# USB-ESP32.net
KiCad netlist of a schematic drawn in Altium Designer
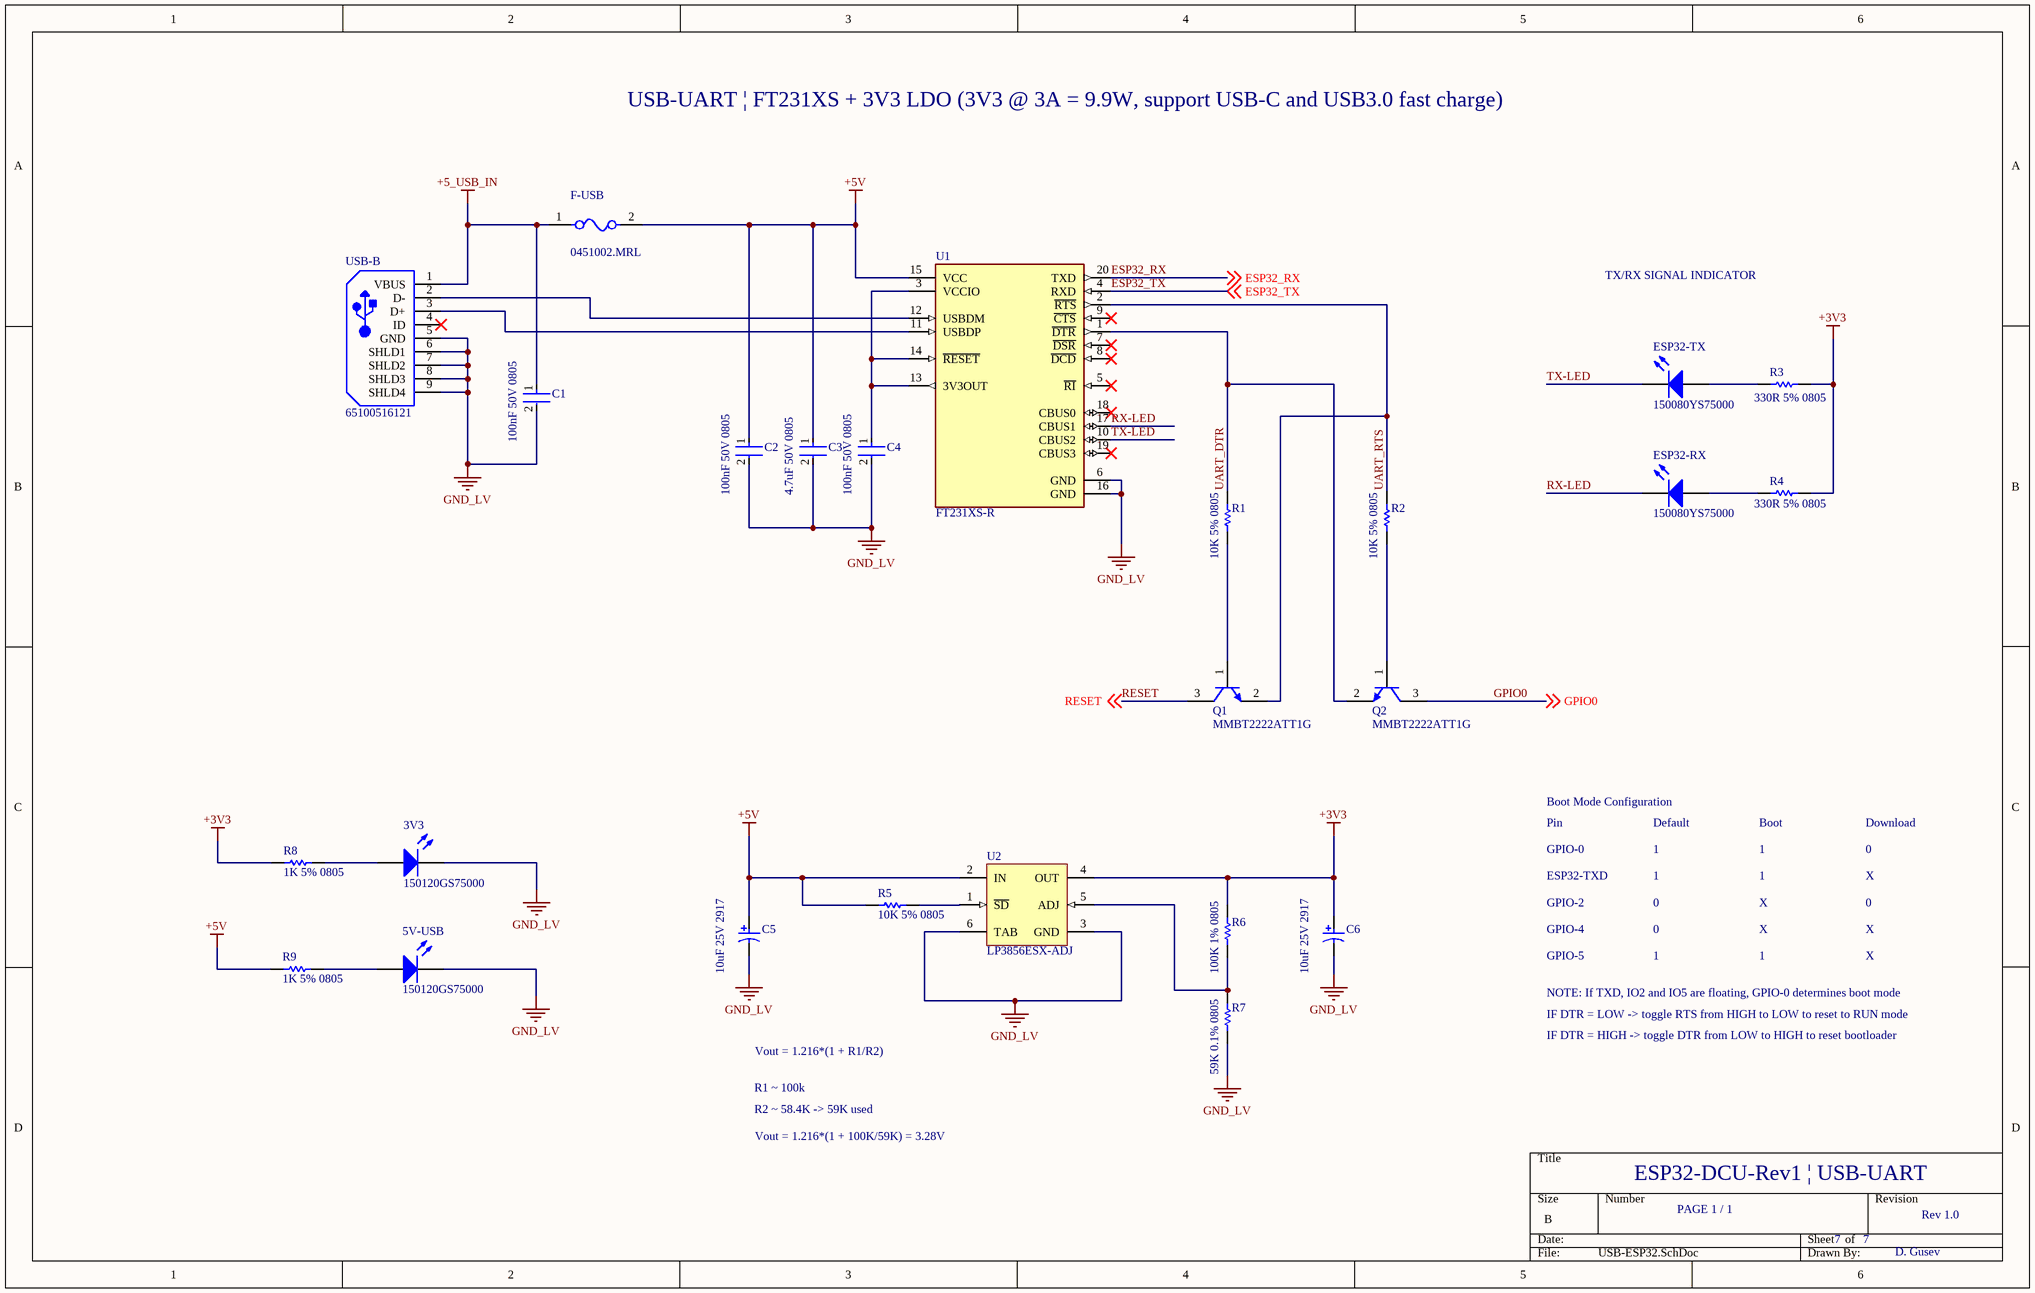
[diagram p0: USB-ESP32.SchDoc]

(export (version "E")
  (design (tool "Eeschema 10.0.6"))
  (components
    (comp (ref "3V3")
      (value "150120GS75000")
      (footprint "1206_A")
      (description "SMD mono-color Chip LED, WL-SMCW, Green")
      (fields (field (name "MANUFACTURER") "Wuerth Elektronik"))
      (libsource (lib "Altium Content Vault") (part "WE-LED_K1A2-2"))
    )
    (comp (ref "5V-USB")
      (value "150120GS75000")
      (footprint "1206_A")
      (description "SMD mono-color Chip LED, WL-SMCW, Green")
      (fields (field (name "MANUFACTURER") "Wuerth Elektronik"))
      (libsource (lib "Altium Content Vault") (part "WE-LED_K1A2-2"))
    )
    (comp (ref "C1")
      (value "100nF 50V 0805")
      (footprint "FP-C0805C-DN-MFG")
      (description "CAP CER 0.1UF 50V X7R 0805")
      (fields
        (field (name "MANUFACTURER PART NUMBER") "C0805C104K5RACTU")
        (field (name "MANUFACTURER") "KEMET")
      )
      (libsource (lib "Altium Content Vault") (part "b4654b650e69147ec39a6b967a45e02"))
    )
    (comp (ref "C2")
      (value "100nF 50V 0805")
      (footprint "FP-C0805C-DN-MFG")
      (description "CAP CER 0.1UF 50V X7R 0805")
      (fields
        (field (name "MANUFACTURER PART NUMBER") "C0805C104K5RACTU")
        (field (name "MANUFACTURER") "KEMET")
      )
      (libsource (lib "Altium Content Vault") (part "b4654b650e69147ec39a6b967a45e02"))
    )
    (comp (ref "C3")
      (value "4.7uF 50V 0805")
      (footprint "FP-C2012-125-MFG")
      (description "CAP CER 4.7UF 50V X5R 0805")
      (fields
        (field (name "TOLERANCE") "10%")
        (field (name "MANUFACTURER PART NUMBER") "C2012X5R1H475K125AB")
      )
      (libsource (lib "Altium Content Vault") (part "11868f565c42a9108669ba33697ecf6"))
    )
    (comp (ref "C4")
      (value "100nF 50V 0805")
      (footprint "FP-C0805C-DN-MFG")
      (description "CAP CER 0.1UF 50V X7R 0805")
      (fields
        (field (name "MANUFACTURER PART NUMBER") "C0805C104K5RACTU")
        (field (name "MANUFACTURER") "KEMET")
      )
      (libsource (lib "Altium Content Vault") (part "b4654b650e69147ec39a6b967a45e02"))
    )
    (comp (ref "C5")
      (value "10uF 25V 2917")
      (footprint "KEMT-T491-D_L")
      (description "Tantalum Capacitor, 10 uF, +/- 10%, 25 V, -55 to 125 degC, 2-Pin SMD, RoHS, Tape and Reel")
      (fields (field (name "MANUFACTURER") "Kemet") (field (name "VOLTAGE") "25VDC"))
      (libsource (lib "Altium Content Vault") (part "CAP-P-2"))
    )
    (comp (ref "C6")
      (value "10uF 25V 2917")
      (footprint "KEMT-T491-D_L")
      (description "Tantalum Capacitor, 10 uF, +/- 10%, 25 V, -55 to 125 degC, 2-Pin SMD, RoHS, Tape and Reel")
      (fields (field (name "MANUFACTURER") "Kemet") (field (name "VOLTAGE") "25VDC"))
      (libsource (lib "Altium Content Vault") (part "CAP-P-2"))
    )
    (comp (ref "ESP32-RX")
      (value "150080YS75000")
      (footprint "0805_A")
      (description "SMD mono-color Chip LED, WL-SMCW, Yellow")
      (fields (field (name "MANUFACTURER") "Wuerth Elektronik"))
      (libsource (lib "Altium Content Vault") (part "WE-LED_K1A2-2"))
    )
    (comp (ref "ESP32-TX")
      (value "150080YS75000")
      (footprint "0805_A")
      (description "SMD mono-color Chip LED, WL-SMCW, Yellow")
      (fields (field (name "MANUFACTURER") "Wuerth Elektronik"))
      (libsource (lib "Altium Content Vault") (part "WE-LED_K1A2-2"))
    )
    (comp (ref "F-USB")
      (value "0451002.MRL")
      (footprint "FP-0451-MFG")
      (description "FUSE BOARD MNT 2A 125VAC/VDC SMD")
      (fields
        (field (name "MANUFACTURER") "Littelfuse")
        (field (name "OCTOPART") "https://octopart.com/0451002.mrl-littelfuse-566376")
      )
      (libsource (lib "Altium Content Vault") (part "5bcf9b9f640e542cf0359d10258e979"))
    )
    (comp (ref "Q1")
      (value "MMBT2222ATT1G")
      (footprint "ONSC-SC-75-3-463-01_V")
      (description "General Purpose Transistor, NPN Silicon, 3-Pin SC-75, Pb-Free, Tape and Reel")
      (fields (field (name "MANUFACTURER") "On Semiconductor"))
      (libsource (lib "Altium Content Vault") (part "ONSC-NPN-B1E2C3-3"))
    )
    (comp (ref "Q2")
      (value "MMBT2222ATT1G")
      (footprint "ONSC-SC-75-3-463-01_V")
      (description "General Purpose Transistor, NPN Silicon, 3-Pin SC-75, Pb-Free, Tape and Reel")
      (fields (field (name "MANUFACTURER") "On Semiconductor"))
      (libsource (lib "Altium Content Vault") (part "ONSC-NPN-B1E2C3-3"))
    )
    (comp (ref "R1")
      (value "10K 5% 0805")
      (footprint "RESC2013X60X40ML20T25")
      (fields (field (name "PART NUMBER") "ERA6AEB123V") (field (name "MANUFACTURER") "Panasonic"))
      (libsource (lib "Altium Content Vault") (part "RES"))
    )
    (comp (ref "R2")
      (value "10K 5% 0805")
      (footprint "RESC2013X60X40ML20T25")
      (fields (field (name "PART NUMBER") "ERA6AEB123V") (field (name "MANUFACTURER") "Panasonic"))
      (libsource (lib "Altium Content Vault") (part "RES"))
    )
    (comp (ref "R3")
      (value "330R 5% 0805")
      (footprint "RESC2013X60X40ML20T25")
      (fields (field (name "PART NUMBER") "ERA6AEB123V") (field (name "MANUFACTURER") "Panasonic"))
      (libsource (lib "Altium Content Vault") (part "RES"))
    )
    (comp (ref "R4")
      (value "330R 5% 0805")
      (footprint "RESC2013X60X40ML20T25")
      (fields (field (name "PART NUMBER") "ERA6AEB123V") (field (name "MANUFACTURER") "Panasonic"))
      (libsource (lib "Altium Content Vault") (part "RES"))
    )
    (comp (ref "R5")
      (value "10K 5% 0805")
      (footprint "RESC2013X60X40ML20T25")
      (fields (field (name "PART NUMBER") "ERA6AEB123V") (field (name "MANUFACTURER") "Panasonic"))
      (libsource (lib "Altium Content Vault") (part "RES"))
    )
    (comp (ref "R6")
      (value "100K 1% 0805")
      (footprint "RESC2013X60X35ML10T20")
      (description "Chip Resistor, 100 KOhm, +/- 1%, 0.125 W, -55 to 155 degC, 0805 (2012 Metric), RoHS, Tape and Reel")
      (fields (field (name "MANUFACTURER") "Yageo") (field (name "TOLERANCE") "1%"))
      (libsource (lib "Altium Content Vault") (part "RES-2"))
    )
    (comp (ref "R7")
      (value "59K 0.1% 0805")
      (footprint "RESC2013X60X35NL10T20")
      (fields (field (name "PART NUMBER") "RC0805FR-0759KL") (field (name "MANUFACTURER") "Yageo"))
      (libsource (lib "Altium Content Vault") (part "RES"))
    )
    (comp (ref "R8")
      (value "1K 5% 0805")
      (footprint "RESC2013X60X40ML20T25")
      (fields (field (name "PART NUMBER") "ERA6AEB123V") (field (name "MANUFACTURER") "Panasonic"))
      (libsource (lib "Altium Content Vault") (part "RES"))
    )
    (comp (ref "R9")
      (value "1K 5% 0805")
      (footprint "RESC2013X60X40ML20T25")
      (fields (field (name "PART NUMBER") "ERA6AEB123V") (field (name "MANUFACTURER") "Panasonic"))
      (libsource (lib "Altium Content Vault") (part "RES"))
    )
    (comp (ref "U1")
      (value "FT231XS-R")
      (footprint "FP-SSOP-20-MFG")
      (description "IC USB SERIAL FULL UART 20SSOP")
      (libsource (lib "Altium Content Vault") (part "6ea930917329caabf1041b50a9b81b2"))
    )
    (comp (ref "U2")
      (value "LP3856ESX-ADJ")
      (footprint "TS5B_M")
      (description "3A Fast Ultra Low Dropout Linear Regulator, 5-pin TO-263")
      (fields (field (name "MANUFACTURER") "National Semiconductor"))
      (libsource (lib "Altium Content Vault") (part "PM-REG-LP3874ADJ-SIL6"))
    )
    (comp (ref "USB-B")
      (value "65100516121")
      (footprint "WE-65100516121_V")
      (description "MINI USB 2.0 SMT Type B 5 Contacts, 30 V, -40 to 105 degC, RoHS, Tape and Reel")
      (fields (field (name "MANUFACTURER") "Wuerth Elektronik"))
      (libsource (lib "Altium Content Vault") (part "USB-5-4SHLD"))
    )
  )
  (nets
    (net (code "1") (name "+3V3") (class "Default")
      (node (ref "C6") (pin "1") (pinfunction "1_1") (pintype "passive"))
      (node (ref "R3") (pin "1") (pinfunction "1_1") (pintype "passive"))
      (node (ref "R4") (pin "1") (pinfunction "1_1") (pintype "passive"))
      (node (ref "R6") (pin "2") (pinfunction "2_2") (pintype "passive"))
      (node (ref "R8") (pin "2") (pinfunction "2_2") (pintype "passive"))
      (node (ref "U2") (pin "4") (pinfunction "OUT_4") (pintype "power_in"))
    )
    (net (code "2") (name "+5V") (class "Default")
      (node (ref "C2") (pin "1") (pinfunction "1_1") (pintype "passive"))
      (node (ref "C3") (pin "1") (pinfunction "1_1") (pintype "passive"))
      (node (ref "C5") (pin "1") (pinfunction "1_1") (pintype "passive"))
      (node (ref "F-USB") (pin "2") (pinfunction "2_2") (pintype "passive"))
      (node (ref "R5") (pin "2") (pinfunction "2_2") (pintype "passive"))
      (node (ref "R9") (pin "2") (pinfunction "2_2") (pintype "passive"))
      (node (ref "U1") (pin "15") (pinfunction "VCC_15") (pintype "power_in"))
      (node (ref "U2") (pin "2") (pinfunction "IN_2") (pintype "power_in"))
    )
    (net (code "3") (name "+5_USB_IN") (class "Default")
      (node (ref "C1") (pin "1") (pinfunction "1_1") (pintype "passive"))
      (node (ref "F-USB") (pin "1") (pinfunction "1_1") (pintype "passive"))
      (node (ref "USB-B") (pin "1") (pinfunction "VBUS_1") (pintype "power_in"))
    )
    (net (code "4") (name "/RX-LED") (class "Default")
      (node (ref "ESP32-RX") (pin "1") (pinfunction "K_1") (pintype "passive"))
      (node (ref "U1") (pin "17") (pinfunction "CBUS1_17") (pintype "bidirectional"))
    )
    (net (code "5") (name "/TX-LED") (class "Default")
      (node (ref "ESP32-TX") (pin "1") (pinfunction "K_1") (pintype "passive"))
      (node (ref "U1") (pin "10") (pinfunction "CBUS2_10") (pintype "bidirectional"))
    )
    (net (code "6") (name "/UART_DTR") (class "Default")
      (node (ref "Q2") (pin "2") (pinfunction "E_2") (pintype "passive"))
      (node (ref "R1") (pin "2") (pinfunction "2_2") (pintype "passive"))
      (node (ref "U1") (pin "1") (pinfunction "~{DTR}_1") (pintype "output"))
    )
    (net (code "7") (name "/UART_RTS") (class "Default")
      (node (ref "Q1") (pin "2") (pinfunction "E_2") (pintype "passive"))
      (node (ref "R2") (pin "2") (pinfunction "2_2") (pintype "passive"))
      (node (ref "U1") (pin "2") (pinfunction "~{RTS}_2") (pintype "output"))
    )
    (net (code "8") (name "ESP32_RX") (class "Default")
      (node (ref "U1") (pin "20") (pinfunction "TXD_20") (pintype "output"))
    )
    (net (code "9") (name "ESP32_TX") (class "Default")
      (node (ref "U1") (pin "4") (pinfunction "RXD_4") (pintype "input"))
    )
    (net (code "10") (name "GND_LV") (class "Default")
      (node (ref "3V3") (pin "1") (pinfunction "K_1") (pintype "passive"))
      (node (ref "5V-USB") (pin "1") (pinfunction "K_1") (pintype "passive"))
      (node (ref "C1") (pin "2") (pinfunction "2_2") (pintype "passive"))
      (node (ref "C2") (pin "2") (pinfunction "2_2") (pintype "passive"))
      (node (ref "C3") (pin "2") (pinfunction "2_2") (pintype "passive"))
      (node (ref "C4") (pin "2") (pinfunction "2_2") (pintype "passive"))
      (node (ref "C5") (pin "2") (pinfunction "2_2") (pintype "passive"))
      (node (ref "C6") (pin "2") (pinfunction "2_2") (pintype "passive"))
      (node (ref "R7") (pin "1") (pinfunction "1_1") (pintype "passive"))
      (node (ref "U1") (pin "16") (pinfunction "GND_16") (pintype "power_in"))
      (node (ref "U1") (pin "6") (pinfunction "GND_6") (pintype "power_in"))
      (node (ref "U2") (pin "3") (pinfunction "GND_3") (pintype "power_in"))
      (node (ref "U2") (pin "6") (pinfunction "TAB_6") (pintype "power_in"))
      (node (ref "USB-B") (pin "5") (pinfunction "GND_5") (pintype "power_in"))
      (node (ref "USB-B") (pin "6") (pinfunction "SHLD1_6") (pintype "passive"))
      (node (ref "USB-B") (pin "7") (pinfunction "SHLD2_7") (pintype "passive"))
      (node (ref "USB-B") (pin "8") (pinfunction "SHLD3_8") (pintype "passive"))
      (node (ref "USB-B") (pin "9") (pinfunction "SHLD4_9") (pintype "passive"))
    )
    (net (code "11") (name "GPIO0") (class "Default")
      (node (ref "Q2") (pin "3") (pinfunction "C_3") (pintype "passive"))
    )
    (net (code "12") (name "Net-(3V3-A)") (class "Default")
      (node (ref "3V3") (pin "2") (pinfunction "A_2") (pintype "passive"))
      (node (ref "R8") (pin "1") (pinfunction "1_1") (pintype "passive"))
    )
    (net (code "13") (name "Net-(5V-USB-A)") (class "Default")
      (node (ref "5V-USB") (pin "2") (pinfunction "A_2") (pintype "passive"))
      (node (ref "R9") (pin "1") (pinfunction "1_1") (pintype "passive"))
    )
    (net (code "14") (name "Net-(ESP32-RX-A)") (class "Default")
      (node (ref "ESP32-RX") (pin "2") (pinfunction "A_2") (pintype "passive"))
      (node (ref "R4") (pin "2") (pinfunction "2_2") (pintype "passive"))
    )
    (net (code "15") (name "Net-(ESP32-TX-A)") (class "Default")
      (node (ref "ESP32-TX") (pin "2") (pinfunction "A_2") (pintype "passive"))
      (node (ref "R3") (pin "2") (pinfunction "2_2") (pintype "passive"))
    )
    (net (code "16") (name "Net-(Q1-B)") (class "Default")
      (node (ref "Q1") (pin "1") (pinfunction "B_1") (pintype "passive"))
      (node (ref "R1") (pin "1") (pinfunction "1_1") (pintype "passive"))
    )
    (net (code "17") (name "Net-(Q2-B)") (class "Default")
      (node (ref "Q2") (pin "1") (pinfunction "B_1") (pintype "passive"))
      (node (ref "R2") (pin "1") (pinfunction "1_1") (pintype "passive"))
    )
    (net (code "18") (name "Net-(U1-3V3OUT)") (class "Default")
      (node (ref "C4") (pin "1") (pinfunction "1_1") (pintype "passive"))
      (node (ref "U1") (pin "13") (pinfunction "3V3OUT_13") (pintype "output"))
      (node (ref "U1") (pin "14") (pinfunction "~{RESET}_14") (pintype "input"))
      (node (ref "U1") (pin "3") (pinfunction "VCCIO_3") (pintype "power_in"))
    )
    (net (code "19") (name "Net-(U1-USBDM)") (class "Default")
      (node (ref "U1") (pin "12") (pinfunction "USBDM_12") (pintype "input"))
      (node (ref "USB-B") (pin "2") (pinfunction "D-_2") (pintype "passive"))
    )
    (net (code "20") (name "Net-(U1-USBDP)") (class "Default")
      (node (ref "U1") (pin "11") (pinfunction "USBDP_11") (pintype "input"))
      (node (ref "USB-B") (pin "3") (pinfunction "D+_3") (pintype "passive"))
    )
    (net (code "21") (name "Net-(U2-ADJ)") (class "Default")
      (node (ref "R6") (pin "1") (pinfunction "1_1") (pintype "passive"))
      (node (ref "R7") (pin "2") (pinfunction "2_2") (pintype "passive"))
      (node (ref "U2") (pin "5") (pinfunction "ADJ_5") (pintype "input"))
    )
    (net (code "22") (name "Net-(U2-~{SD})") (class "Default")
      (node (ref "R5") (pin "1") (pinfunction "1_1") (pintype "passive"))
      (node (ref "U2") (pin "1") (pinfunction "~{SD}_1") (pintype "input"))
    )
    (net (code "23") (name "RESET") (class "Default")
      (node (ref "Q1") (pin "3") (pinfunction "C_3") (pintype "passive"))
    )
    (net (code "24") (name "unconnected-(U1-CBUS0-Pad18)") (class "Default")
      (node (ref "U1") (pin "18") (pinfunction "CBUS0_18") (pintype "bidirectional+no_connect"))
    )
    (net (code "25") (name "unconnected-(U1-CBUS3-Pad19)") (class "Default")
      (node (ref "U1") (pin "19") (pinfunction "CBUS3_19") (pintype "bidirectional+no_connect"))
    )
    (net (code "26") (name "unconnected-(U1-~{CTS}-Pad9)") (class "Default")
      (node (ref "U1") (pin "9") (pinfunction "~{CTS}_9") (pintype "input+no_connect"))
    )
    (net (code "27") (name "unconnected-(U1-~{DCD}-Pad8)") (class "Default")
      (node (ref "U1") (pin "8") (pinfunction "~{DCD}_8") (pintype "input+no_connect"))
    )
    (net (code "28") (name "unconnected-(U1-~{DSR}-Pad7)") (class "Default")
      (node (ref "U1") (pin "7") (pinfunction "~{DSR}_7") (pintype "input+no_connect"))
    )
    (net (code "29") (name "unconnected-(U1-~{RI}-Pad5)") (class "Default")
      (node (ref "U1") (pin "5") (pinfunction "~{RI}_5") (pintype "input+no_connect"))
    )
    (net (code "30") (name "unconnected-(USB-B-ID-Pad4)") (class "Default")
      (node (ref "USB-B") (pin "4") (pinfunction "ID_4") (pintype "passive+no_connect"))
    )
  )
)
